# tritiled22_cr2354_oslon.net
KiCad netlist of a schematic drawn in EAGLE
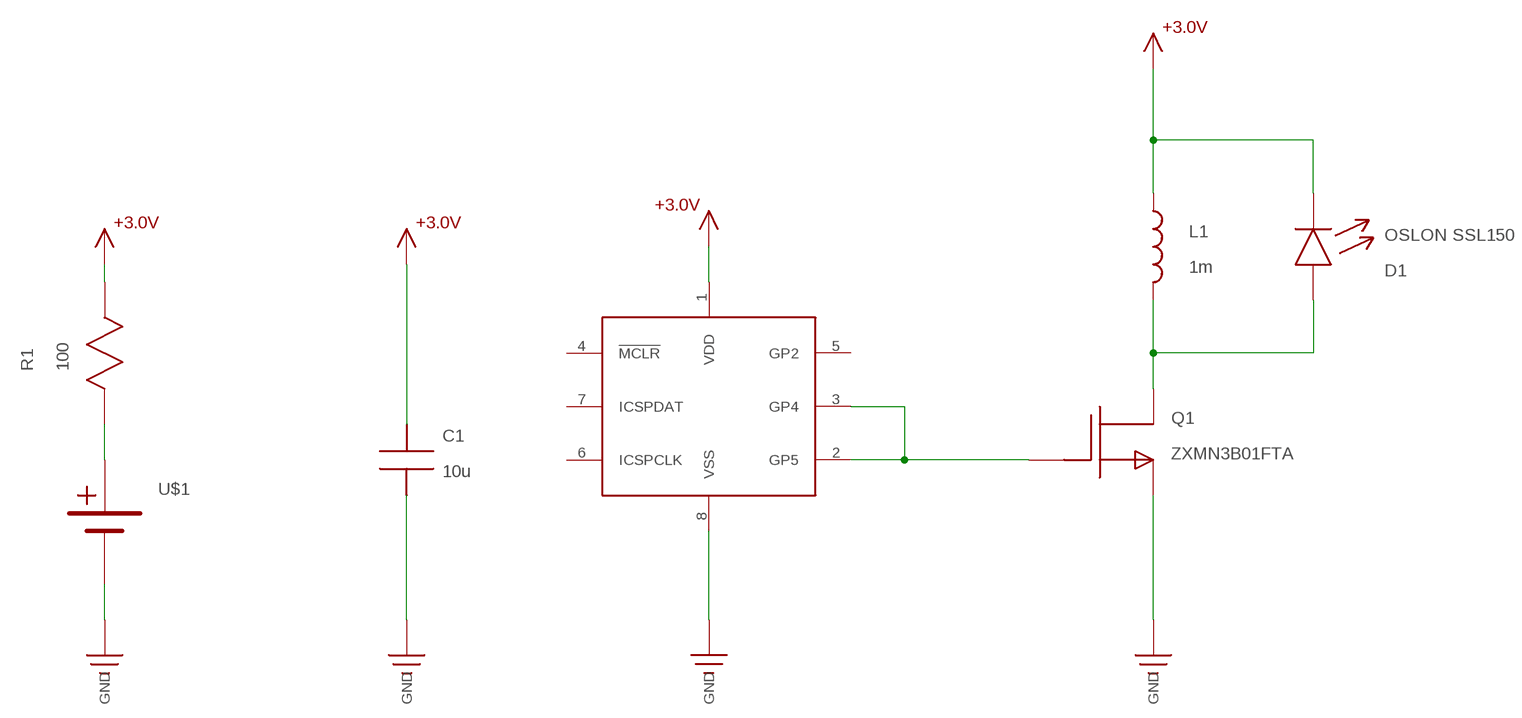
[diagram p0: schematic, sheet 1]

(export (version "E")
  (design (tool "Eeschema 10.0.6"))
  (components
    (comp (ref "C1")
      (value "10u")
      (footprint "eagle-import:1206")
      (libsource (lib "eagle-import") (part "C1206"))
    )
    (comp (ref "D1")
      (value "OSLON SSL150")
      (footprint "eagle-import:OSLON_3030_LED")
      (libsource (lib "eagle-import") (part "LEDSSL150"))
    )
    (comp (ref "L1")
      (value "1m")
      (footprint "eagle-import:SRR6028_INDUCTOR")
      (libsource (lib "eagle-import") (part "SRR6028_INDUCTOR"))
    )
    (comp (ref "Q1")
      (value "ZXMN3B01FTA")
      (footprint "eagle-import:SOT-23")
      (libsource (lib "eagle-import") (part "ZXMN3B01FSOT23"))
    )
    (comp (ref "R1")
      (value "100")
      (footprint "eagle-import:R1206")
      (libsource (lib "eagle-import") (part "R1206"))
    )
    (comp (ref "U$1")
      (value "CR2354_TABBED")
      (footprint "eagle-import:CR2354_TABBED")
      (libsource (lib "eagle-import") (part "CR2354_TABBED"))
    )
    (comp (ref "U1")
      (value "PIC12LF1571")
      (footprint "eagle-import:SOIC8")
      (libsource (lib "eagle-import") (part "PIC12LF1571"))
    )
  )
  (nets
    (net (code "1") (name "+3.0V") (class "Default")
      (node (ref "C1") (pin "P$1") (pinfunction "P$1_P$1") (pintype "bidirectional"))
      (node (ref "D1") (pin "C") (pinfunction "C_C") (pintype "bidirectional"))
      (node (ref "L1") (pin "P$1") (pinfunction "1_P$1") (pintype "passive"))
      (node (ref "R1") (pin "P$2") (pinfunction "P$2_P$2") (pintype "bidirectional"))
      (node (ref "U1") (pin "1") (pinfunction "VDD_1") (pintype "bidirectional"))
    )
    (net (code "2") (name "GND") (class "Default")
      (node (ref "C1") (pin "P$2") (pinfunction "P$2_P$2") (pintype "bidirectional"))
      (node (ref "Q1") (pin "2") (pinfunction "S_2") (pintype "bidirectional"))
      (node (ref "U$1") (pin "GND") (pinfunction "0V_GND") (pintype "power_in"))
      (node (ref "U1") (pin "8") (pinfunction "VSS_8") (pintype "bidirectional"))
    )
    (net (code "3") (name "Net-(L1-2)") (class "Default")
      (node (ref "D1") (pin "A") (pinfunction "A_A") (pintype "bidirectional"))
      (node (ref "L1") (pin "P$2") (pinfunction "2_P$2") (pintype "passive"))
      (node (ref "Q1") (pin "3") (pinfunction "D_3") (pintype "bidirectional"))
    )
    (net (code "4") (name "Net-(Q1-G)") (class "Default")
      (node (ref "Q1") (pin "1") (pinfunction "G_1") (pintype "bidirectional"))
      (node (ref "U1") (pin "2") (pinfunction "GP5_2") (pintype "bidirectional"))
      (node (ref "U1") (pin "3") (pinfunction "GP4_3") (pintype "bidirectional"))
    )
    (net (code "5") (name "Net-(U$1-+V)") (class "Default")
      (node (ref "R1") (pin "P$1") (pinfunction "P$1_P$1") (pintype "bidirectional"))
      (node (ref "U$1") (pin "+3V") (pinfunction "+V_+3V") (pintype "power_in"))
    )
    (net (code "6") (name "unconnected-(U1-GP2-Pad5)") (class "Default")
      (node (ref "U1") (pin "5") (pinfunction "GP2_5") (pintype "bidirectional"))
    )
    (net (code "7") (name "unconnected-(U1-ICSPCLK-Pad6)") (class "Default")
      (node (ref "U1") (pin "6") (pinfunction "ICSPCLK_6") (pintype "bidirectional"))
    )
    (net (code "8") (name "unconnected-(U1-ICSPDAT-Pad7)") (class "Default")
      (node (ref "U1") (pin "7") (pinfunction "ICSPDAT_7") (pintype "bidirectional"))
    )
    (net (code "9") (name "unconnected-(U1-~{MCLR}-Pad4)") (class "Default")
      (node (ref "U1") (pin "4") (pinfunction "~{MCLR}_4") (pintype "bidirectional"))
    )
  )
)
